# ga_module.net
KiCad netlist of a schematic drawn in EAGLE
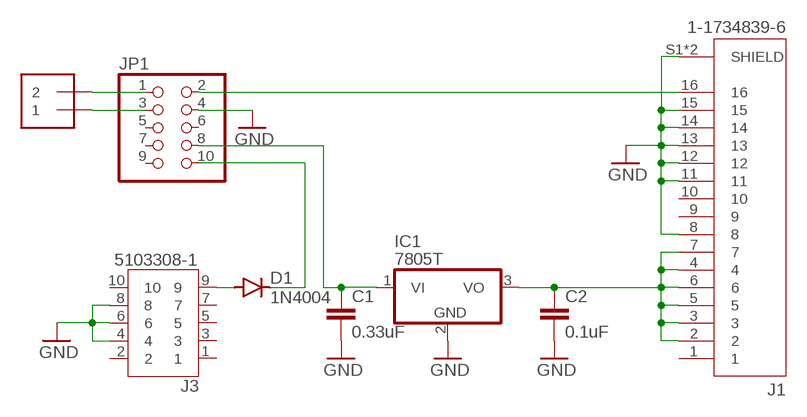
[diagram p0: schematic, sheet 1]

(export (version "E")
  (design (tool "Eeschema 10.0.6"))
  (components
    (comp (ref "C1")
      (value "0.33uF")
      (footprint "eagle-import:CAP-PTH-SMALL-KIT")
      (libsource (lib "eagle-import") (part "0.1UF-KIT-EZ-50V-20%"))
    )
    (comp (ref "C2")
      (value "0.1uF")
      (footprint "eagle-import:CAP-PTH-SMALL-KIT")
      (libsource (lib "eagle-import") (part "0.1UF-KIT-EZ-50V-20%"))
    )
    (comp (ref "D1")
      (value "1N4004")
      (footprint "eagle-import:DO41-10")
      (libsource (lib "eagle-import") (part "1N4004"))
    )
    (comp (ref "IC1")
      (value "7805T")
      (footprint "eagle-import:TO220H")
      (libsource (lib "eagle-import") (part "78T05"))
    )
    (comp (ref "J1")
      (value "1-1734839-6")
      (footprint "eagle-import:TE_1-1734839-6")
      (fields (field (name "MF") "TE Connectivity"))
      (libsource (lib "eagle-import") (part "1-1734839-6"))
    )
    (comp (ref "J2")
      (value "1X2-3.5MM")
      (footprint "eagle-import:1X2-3.5MM")
      (libsource (lib "eagle-import") (part "1X2-3.5MM"))
    )
    (comp (ref "J3")
      (value "5103308-1")
      (footprint "eagle-import:TE_5103308-1")
      (fields (field (name "MF") "TE Connectivity"))
      (libsource (lib "eagle-import") (part "5103308-1"))
    )
    (comp (ref "JP1")
      (value "PINHD-2X5/90")
      (footprint "eagle-import:2X05_90")
      (libsource (lib "eagle-import") (part "PINHD-2X5/90"))
    )
  )
  (nets
    (net (code "1") (name "GND") (class "Default")
      (node (ref "C1") (pin "2") (pinfunction "2_2") (pintype "passive"))
      (node (ref "C2") (pin "2") (pinfunction "2_2") (pintype "passive"))
      (node (ref "IC1") (pin "2") (pinfunction "GND_2") (pintype "passive"))
      (node (ref "J1") (pin "11") (pinfunction "11_11") (pintype "passive"))
      (node (ref "J1") (pin "12") (pinfunction "12_12") (pintype "passive"))
      (node (ref "J1") (pin "13") (pinfunction "13_13") (pintype "passive"))
      (node (ref "J1") (pin "14") (pinfunction "14_14") (pintype "passive"))
      (node (ref "J1") (pin "15") (pinfunction "15_15") (pintype "passive"))
      (node (ref "J1") (pin "8") (pinfunction "8_8") (pintype "passive"))
      (node (ref "J1") (pin "S1") (pinfunction "SHIELD_S1") (pintype "passive"))
      (node (ref "J1") (pin "S2") (pinfunction "SHIELD_S2") (pintype "passive"))
      (node (ref "J3") (pin "4") (pinfunction "4_4") (pintype "passive"))
      (node (ref "J3") (pin "6") (pinfunction "6_6") (pintype "passive"))
      (node (ref "J3") (pin "8") (pinfunction "8_8") (pintype "passive"))
      (node (ref "JP1") (pin "4") (pinfunction "4_4") (pintype "passive"))
    )
    (net (code "2") (name "Net-(D1-PadA)") (class "Default")
      (node (ref "D1") (pin "A") (pinfunction "A_A") (pintype "passive"))
      (node (ref "J3") (pin "9") (pinfunction "9_9") (pintype "passive"))
    )
    (net (code "3") (name "Net-(D1-PadC)") (class "Default")
      (node (ref "D1") (pin "C") (pinfunction "C_C") (pintype "passive"))
      (node (ref "JP1") (pin "10") (pinfunction "10_10") (pintype "passive"))
    )
    (net (code "4") (name "Net-(IC1-VI)") (class "Default")
      (node (ref "C1") (pin "1") (pinfunction "1_1") (pintype "passive"))
      (node (ref "IC1") (pin "1") (pinfunction "VI_1") (pintype "input"))
      (node (ref "JP1") (pin "8") (pinfunction "8_8") (pintype "passive"))
    )
    (net (code "5") (name "Net-(IC1-VO)") (class "Default")
      (node (ref "C2") (pin "1") (pinfunction "1_1") (pintype "passive"))
      (node (ref "IC1") (pin "3") (pinfunction "VO_3") (pintype "passive"))
      (node (ref "J1") (pin "2") (pinfunction "2_2") (pintype "passive"))
      (node (ref "J1") (pin "3") (pinfunction "3_3") (pintype "passive"))
      (node (ref "J1") (pin "4") (pinfunction "4_4") (pintype "passive"))
      (node (ref "J1") (pin "5") (pinfunction "5_5") (pintype "passive"))
      (node (ref "J1") (pin "6") (pinfunction "6_6") (pintype "passive"))
      (node (ref "J1") (pin "7") (pinfunction "7_7") (pintype "passive"))
    )
    (net (code "6") (name "Net-(J1-Pad16)") (class "Default")
      (node (ref "J1") (pin "16") (pinfunction "16_16") (pintype "passive"))
      (node (ref "JP1") (pin "2") (pinfunction "2_2") (pintype "passive"))
    )
    (net (code "7") (name "Net-(J2-Pad1)") (class "Default")
      (node (ref "J2") (pin "1") (pinfunction "1_1") (pintype "passive"))
      (node (ref "JP1") (pin "3") (pinfunction "3_3") (pintype "passive"))
    )
    (net (code "8") (name "Net-(J2-Pad2)") (class "Default")
      (node (ref "J2") (pin "2") (pinfunction "2_2") (pintype "passive"))
      (node (ref "JP1") (pin "1") (pinfunction "1_1") (pintype "passive"))
    )
    (net (code "9") (name "unconnected-(J1-Pad1)") (class "Default")
      (node (ref "J1") (pin "1") (pinfunction "1_1") (pintype "passive"))
    )
    (net (code "10") (name "unconnected-(J1-Pad9)") (class "Default")
      (node (ref "J1") (pin "9") (pinfunction "9_9") (pintype "passive"))
    )
    (net (code "11") (name "unconnected-(J1-Pad10)") (class "Default")
      (node (ref "J1") (pin "10") (pinfunction "10_10") (pintype "passive"))
    )
    (net (code "12") (name "unconnected-(J3-Pad1)") (class "Default")
      (node (ref "J3") (pin "1") (pinfunction "1_1") (pintype "passive"))
    )
    (net (code "13") (name "unconnected-(J3-Pad2)") (class "Default")
      (node (ref "J3") (pin "2") (pinfunction "2_2") (pintype "passive"))
    )
    (net (code "14") (name "unconnected-(J3-Pad3)") (class "Default")
      (node (ref "J3") (pin "3") (pinfunction "3_3") (pintype "passive"))
    )
    (net (code "15") (name "unconnected-(J3-Pad5)") (class "Default")
      (node (ref "J3") (pin "5") (pinfunction "5_5") (pintype "passive"))
    )
    (net (code "16") (name "unconnected-(J3-Pad7)") (class "Default")
      (node (ref "J3") (pin "7") (pinfunction "7_7") (pintype "passive"))
    )
    (net (code "17") (name "unconnected-(J3-Pad10)") (class "Default")
      (node (ref "J3") (pin "10") (pinfunction "10_10") (pintype "passive"))
    )
    (net (code "18") (name "unconnected-(JP1-Pad5)") (class "Default")
      (node (ref "JP1") (pin "5") (pinfunction "5_5") (pintype "passive"))
    )
    (net (code "19") (name "unconnected-(JP1-Pad6)") (class "Default")
      (node (ref "JP1") (pin "6") (pinfunction "6_6") (pintype "passive"))
    )
    (net (code "20") (name "unconnected-(JP1-Pad7)") (class "Default")
      (node (ref "JP1") (pin "7") (pinfunction "7_7") (pintype "passive"))
    )
    (net (code "21") (name "unconnected-(JP1-Pad9)") (class "Default")
      (node (ref "JP1") (pin "9") (pinfunction "9_9") (pintype "passive"))
    )
  )
)
